# carrier_board_simplified.net
KiCad netlist of a schematic drawn in EAGLE
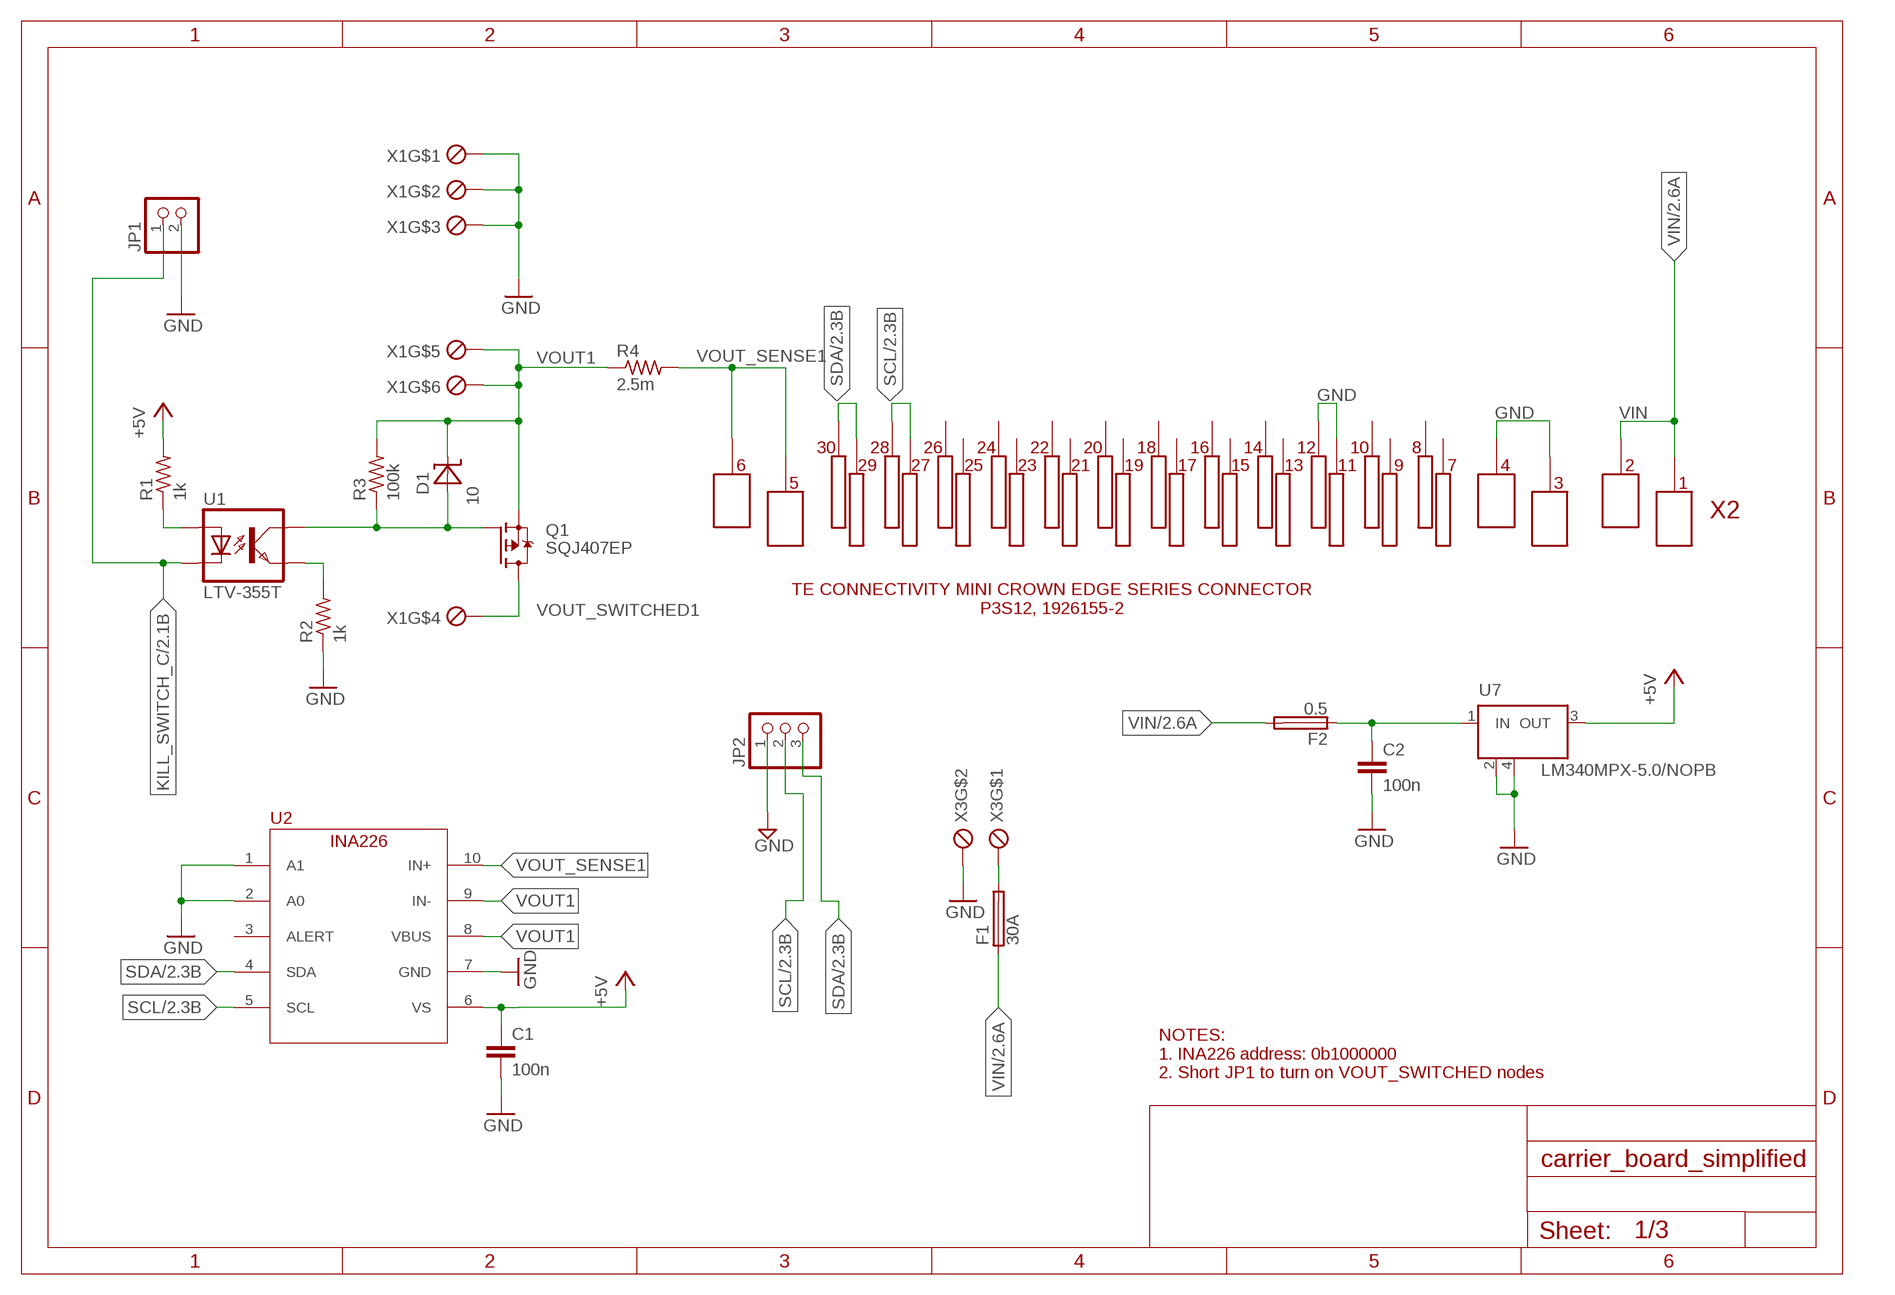
[diagram p0: schematic, sheet 1]
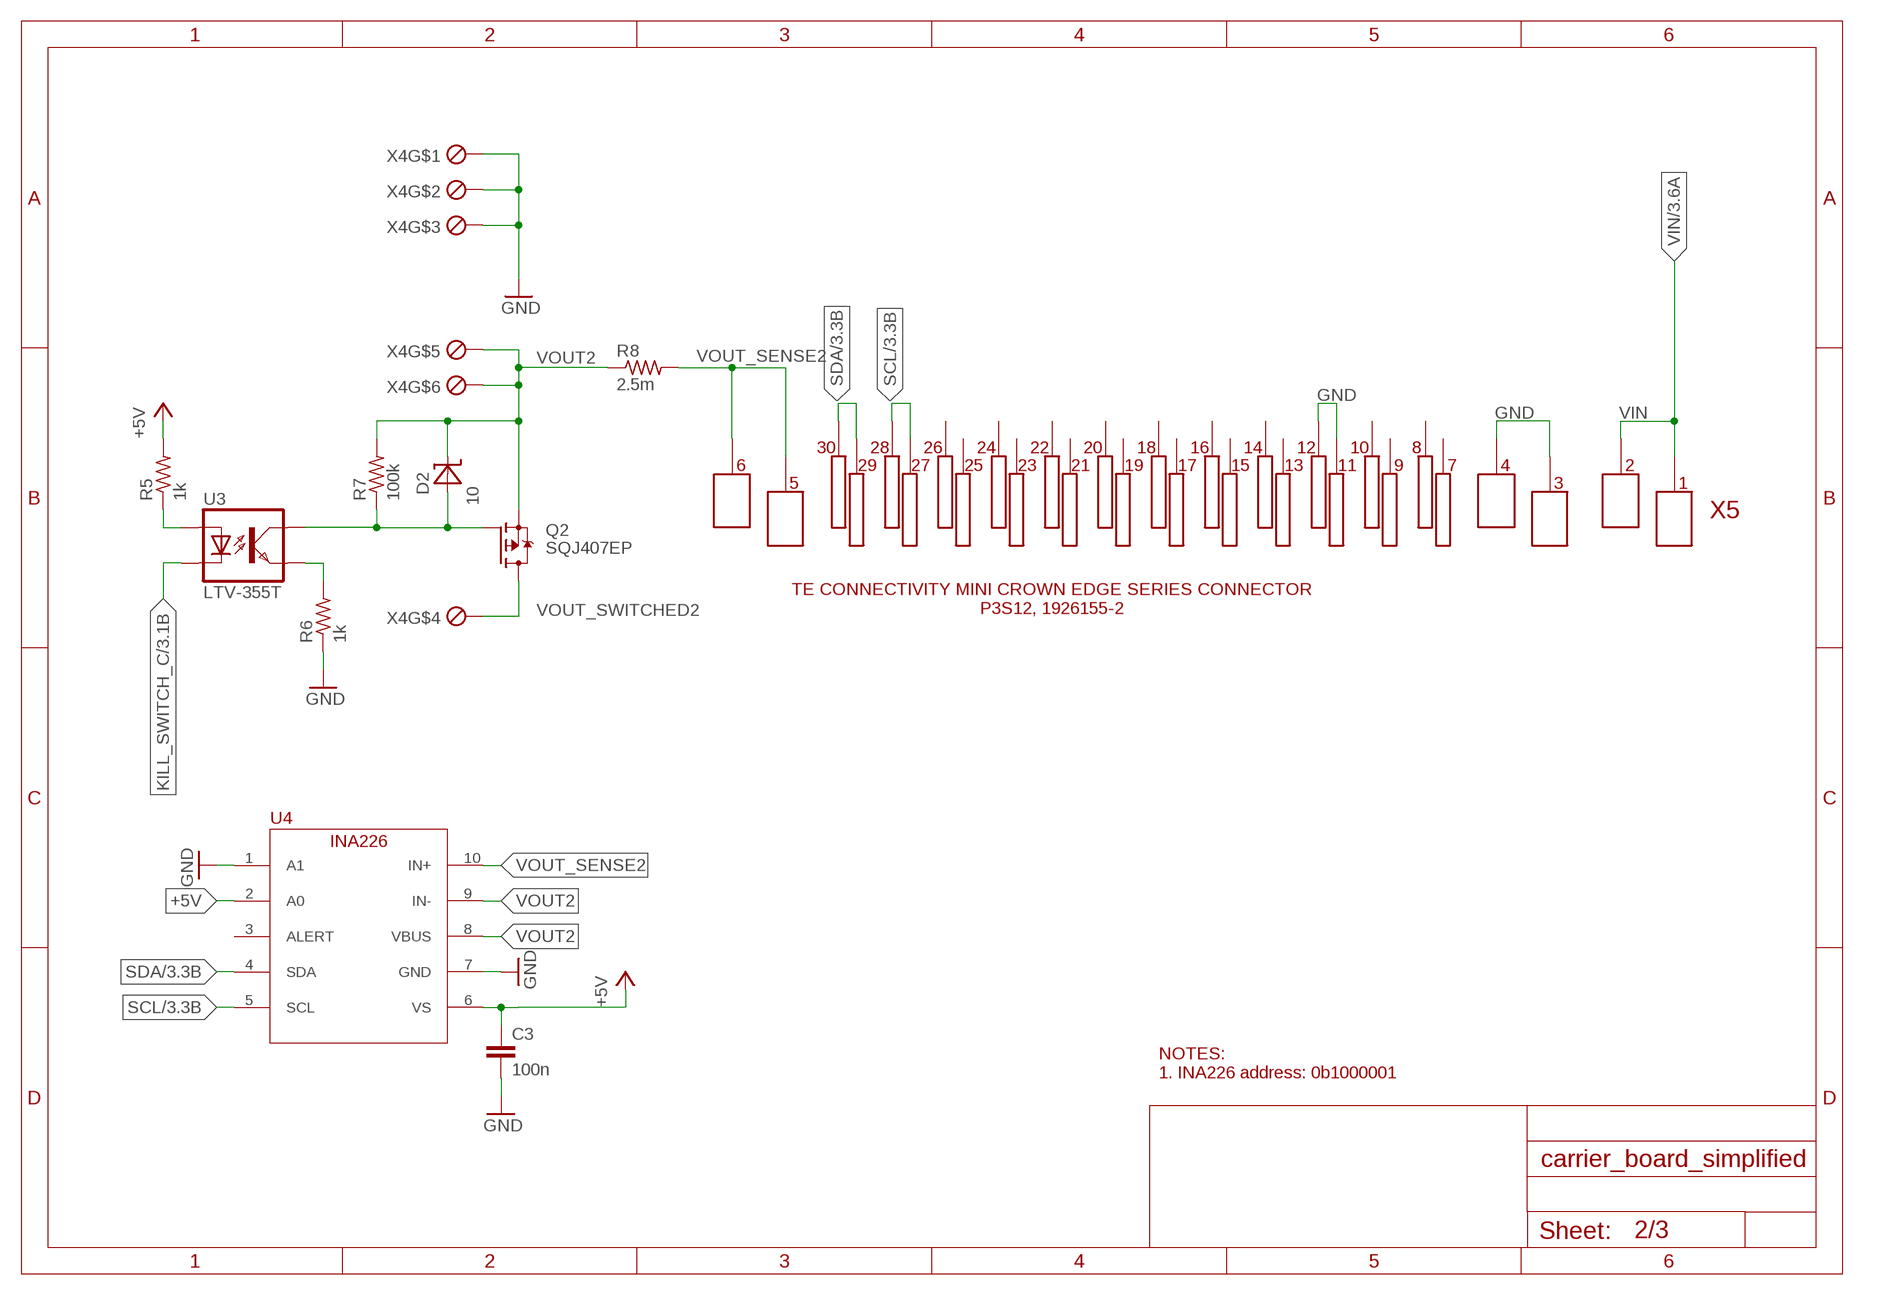
[diagram p1: schematic, sheet 2]
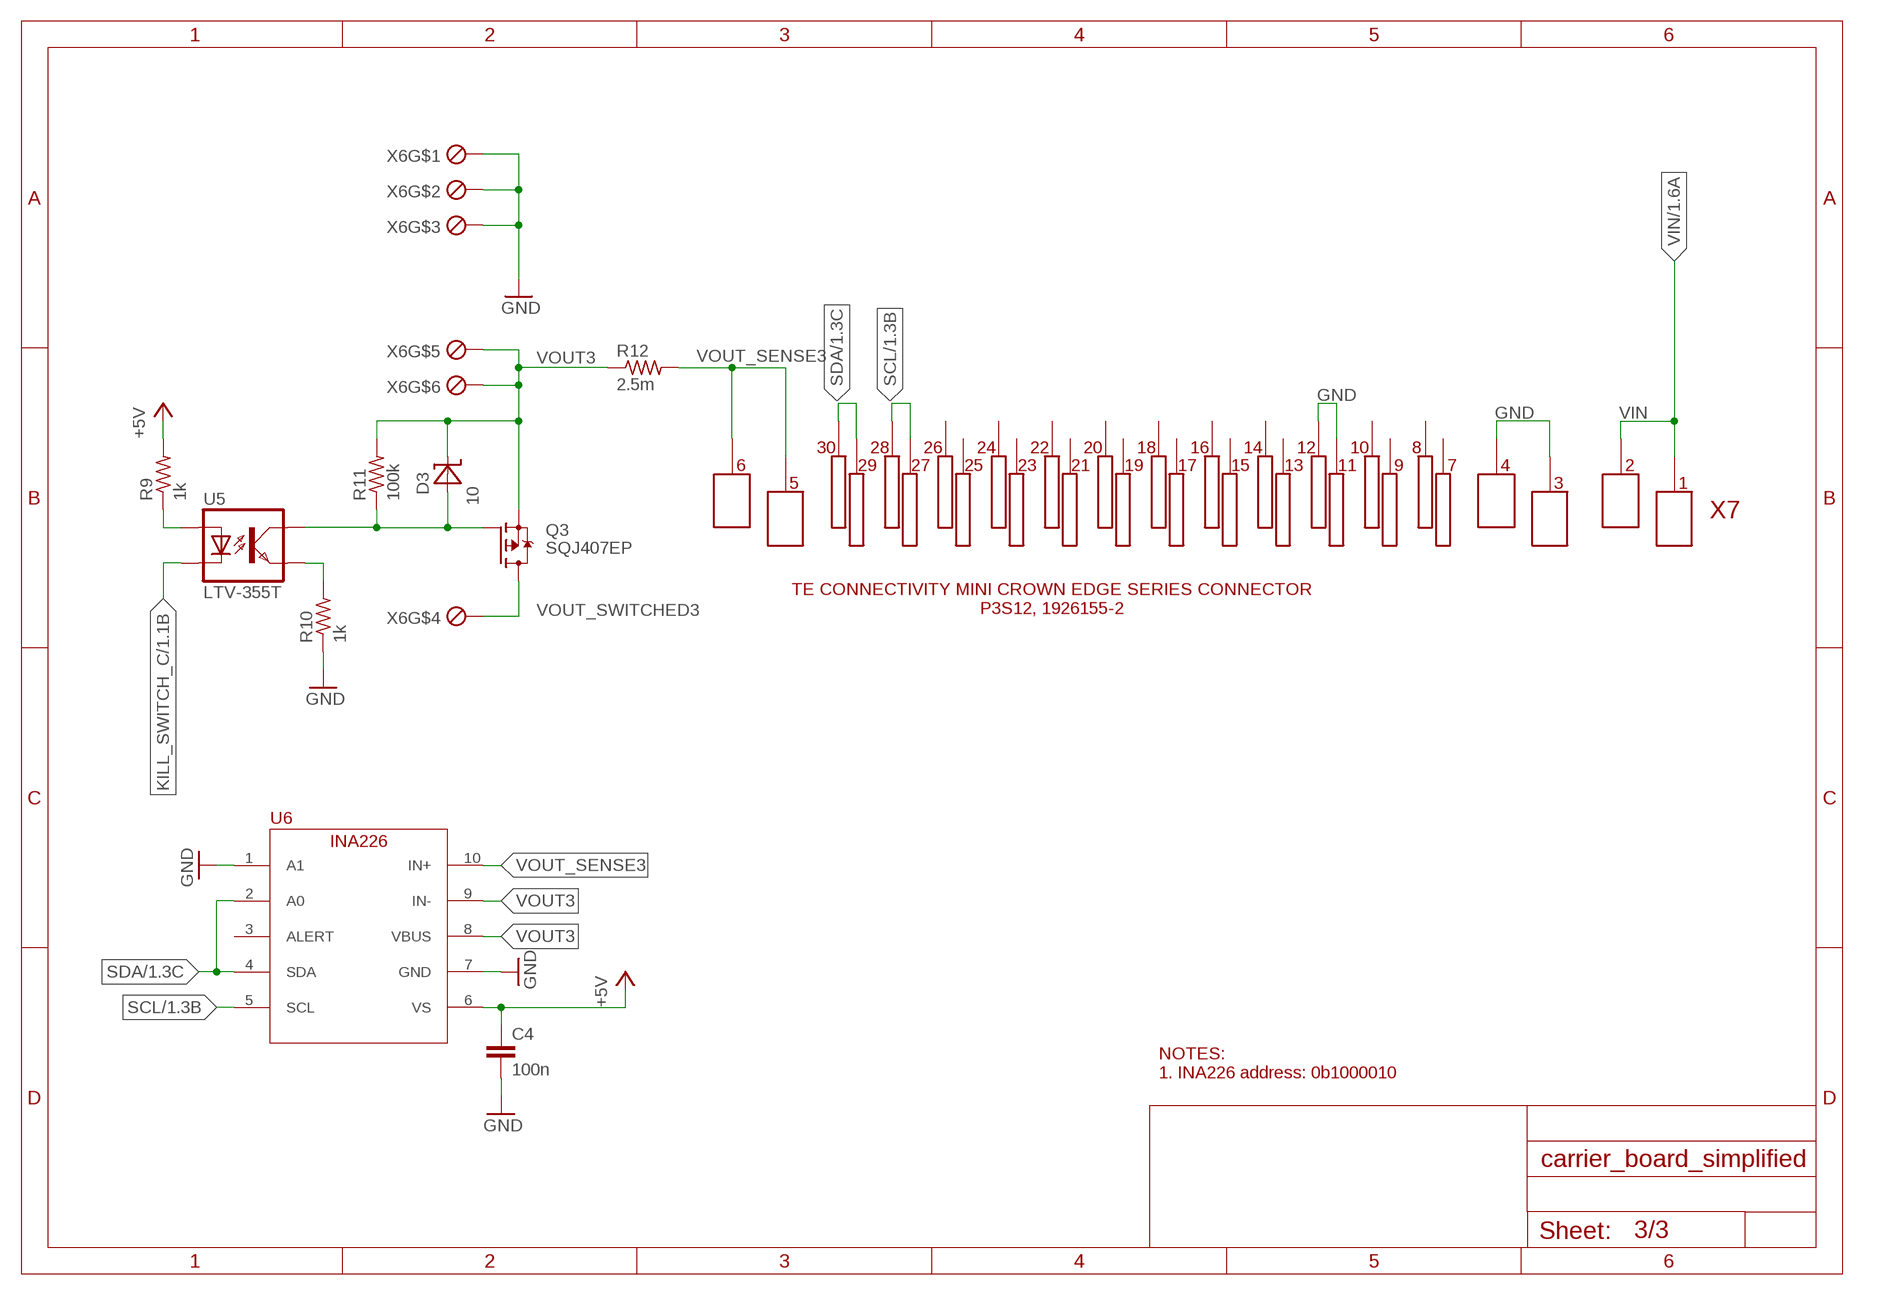
[diagram p2: schematic, sheet 3]

(export (version "E")
  (design (tool "Eeschema 10.0.6"))
  (components
    (comp (ref "C3")
      (value "100n")
      (footprint "eagle-import:C0603")
      (libsource (lib "eagle-import") (part "C-EUC0603"))
    )
    (comp (ref "D2")
      (value "10")
      (footprint "eagle-import:SOD123")
      (libsource (lib "eagle-import") (part "BZT52C10-TP"))
    )
    (comp (ref "Q2")
      (value "SQJ407EP")
      (footprint "eagle-import:POWERPAK_SO8L_SINGLE")
      (libsource (lib "eagle-import") (part "SQJ407EP"))
    )
    (comp (ref "R5")
      (value "1k")
      (footprint "eagle-import:R0603")
      (libsource (lib "eagle-import") (part "R-US_R0603"))
    )
    (comp (ref "R6")
      (value "1k")
      (footprint "eagle-import:R0603")
      (libsource (lib "eagle-import") (part "R-US_R0603"))
    )
    (comp (ref "R7")
      (value "100k")
      (footprint "eagle-import:R0603")
      (libsource (lib "eagle-import") (part "R-US_R0603"))
    )
    (comp (ref "R8")
      (value "2.5m")
      (footprint "eagle-import:R2512")
      (libsource (lib "eagle-import") (part "R-US_R2512"))
    )
    (comp (ref "U3")
      (value "LTV-355T")
      (footprint "eagle-import:SMD4")
      (libsource (lib "eagle-import") (part "LTV-355T"))
    )
    (comp (ref "U4")
      (value "INA226")
      (footprint "eagle-import:MSOP10")
      (libsource (lib "eagle-import") (part "INA226"))
    )
    (comp (ref "X4")
      (value "284391-6")
      (footprint "eagle-import:284391-6")
      (libsource (lib "eagle-import") (part "284391-6"))
    )
    (comp (ref "X5")
      (value "1926155-2_SOCK")
      (footprint "eagle-import:1926155-2_SOCK")
      (libsource (lib "eagle-import") (part "1926155-2_SOCK"))
    )
    (comp (ref "C1")
      (value "100n")
      (footprint "eagle-import:C0603")
      (libsource (lib "eagle-import") (part "C-EUC0603"))
    )
    (comp (ref "C2")
      (value "100n")
      (footprint "eagle-import:C0603")
      (libsource (lib "eagle-import") (part "C-EUC0603"))
    )
    (comp (ref "D1")
      (value "10")
      (footprint "eagle-import:SOD123")
      (libsource (lib "eagle-import") (part "BZT52C10-TP"))
    )
    (comp (ref "F1")
      (value "30A")
      (footprint "eagle-import:3557-10")
      (libsource (lib "eagle-import") (part "3557-10"))
    )
    (comp (ref "F2")
      (value "0.5")
      (footprint "eagle-import:R1206")
      (libsource (lib "eagle-import") (part "501_FUSE"))
    )
    (comp (ref "JP1")
      (value "PINHD-1X02_2.54-SMD-90°")
      (footprint "eagle-import:1X02SMD_90")
      (libsource (lib "eagle-import") (part "PINHD-1X02_2.54-SMD-90°"))
    )
    (comp (ref "JP2")
      (value "PINHD-1X03_2.54-SMD-90°")
      (footprint "eagle-import:1X03SMD_90")
      (libsource (lib "eagle-import") (part "PINHD-1X03_2.54-SMD-90°"))
    )
    (comp (ref "Q1")
      (value "SQJ407EP")
      (footprint "eagle-import:POWERPAK_SO8L_SINGLE")
      (libsource (lib "eagle-import") (part "SQJ407EP"))
    )
    (comp (ref "R1")
      (value "1k")
      (footprint "eagle-import:R0603")
      (libsource (lib "eagle-import") (part "R-US_R0603"))
    )
    (comp (ref "R2")
      (value "1k")
      (footprint "eagle-import:R0603")
      (libsource (lib "eagle-import") (part "R-US_R0603"))
    )
    (comp (ref "R3")
      (value "100k")
      (footprint "eagle-import:R0603")
      (libsource (lib "eagle-import") (part "R-US_R0603"))
    )
    (comp (ref "R4")
      (value "2.5m")
      (footprint "eagle-import:R2512")
      (libsource (lib "eagle-import") (part "R-US_R2512"))
    )
    (comp (ref "U1")
      (value "LTV-355T")
      (footprint "eagle-import:SMD4")
      (libsource (lib "eagle-import") (part "LTV-355T"))
    )
    (comp (ref "U2")
      (value "INA226")
      (footprint "eagle-import:MSOP10")
      (libsource (lib "eagle-import") (part "INA226"))
    )
    (comp (ref "U7")
      (value "LM340MPX-5.0/NOPB")
      (footprint "eagle-import:SOT223")
      (libsource (lib "eagle-import") (part "LM340S"))
    )
    (comp (ref "X1")
      (value "284391-6")
      (footprint "eagle-import:284391-6")
      (libsource (lib "eagle-import") (part "284391-6"))
    )
    (comp (ref "X2")
      (value "1926155-2_SOCK")
      (footprint "eagle-import:1926155-2_SOCK")
      (libsource (lib "eagle-import") (part "1926155-2_SOCK"))
    )
    (comp (ref "X3")
      (value "OSTT7020150")
      (footprint "eagle-import:OSTT7020150")
      (libsource (lib "eagle-import") (part "OSTT7020150"))
    )
    (comp (ref "C4")
      (value "100n")
      (footprint "eagle-import:C0603")
      (libsource (lib "eagle-import") (part "C-EUC0603"))
    )
    (comp (ref "D3")
      (value "10")
      (footprint "eagle-import:SOD123")
      (libsource (lib "eagle-import") (part "BZT52C10-TP"))
    )
    (comp (ref "Q3")
      (value "SQJ407EP")
      (footprint "eagle-import:POWERPAK_SO8L_SINGLE")
      (libsource (lib "eagle-import") (part "SQJ407EP"))
    )
    (comp (ref "R9")
      (value "1k")
      (footprint "eagle-import:R0603")
      (libsource (lib "eagle-import") (part "R-US_R0603"))
    )
    (comp (ref "R10")
      (value "1k")
      (footprint "eagle-import:R0603")
      (libsource (lib "eagle-import") (part "R-US_R0603"))
    )
    (comp (ref "R11")
      (value "100k")
      (footprint "eagle-import:R0603")
      (libsource (lib "eagle-import") (part "R-US_R0603"))
    )
    (comp (ref "R12")
      (value "2.5m")
      (footprint "eagle-import:R2512")
      (libsource (lib "eagle-import") (part "R-US_R2512"))
    )
    (comp (ref "U5")
      (value "LTV-355T")
      (footprint "eagle-import:SMD4")
      (libsource (lib "eagle-import") (part "LTV-355T"))
    )
    (comp (ref "U6")
      (value "INA226")
      (footprint "eagle-import:MSOP10")
      (libsource (lib "eagle-import") (part "INA226"))
    )
    (comp (ref "X6")
      (value "284391-6")
      (footprint "eagle-import:284391-6")
      (libsource (lib "eagle-import") (part "284391-6"))
    )
    (comp (ref "X7")
      (value "1926155-2_SOCK")
      (footprint "eagle-import:1926155-2_SOCK")
      (libsource (lib "eagle-import") (part "1926155-2_SOCK"))
    )
  )
  (nets
    (net (code "1") (name "+5V") (class "Default")
      (node (ref "C1") (pin "1") (pinfunction "1_1") (pintype "passive"))
      (node (ref "C3") (pin "1") (pinfunction "1_1") (pintype "passive"))
      (node (ref "C4") (pin "1") (pinfunction "1_1") (pintype "passive"))
      (node (ref "R1") (pin "2") (pinfunction "2_2") (pintype "passive"))
      (node (ref "R5") (pin "2") (pinfunction "2_2") (pintype "passive"))
      (node (ref "R9") (pin "2") (pinfunction "2_2") (pintype "passive"))
      (node (ref "U2") (pin "6") (pinfunction "VS_6") (pintype "bidirectional"))
      (node (ref "U4") (pin "2") (pinfunction "A0_2") (pintype "bidirectional"))
      (node (ref "U4") (pin "6") (pinfunction "VS_6") (pintype "bidirectional"))
      (node (ref "U6") (pin "6") (pinfunction "VS_6") (pintype "bidirectional"))
      (node (ref "U7") (pin "3") (pinfunction "OUT_3") (pintype "passive"))
    )
    (net (code "2") (name "GND") (class "Default")
      (node (ref "C1") (pin "2") (pinfunction "2_2") (pintype "passive"))
      (node (ref "C2") (pin "2") (pinfunction "2_2") (pintype "passive"))
      (node (ref "C3") (pin "2") (pinfunction "2_2") (pintype "passive"))
      (node (ref "C4") (pin "2") (pinfunction "2_2") (pintype "passive"))
      (node (ref "JP1") (pin "2") (pinfunction "2_2") (pintype "passive"))
      (node (ref "JP2") (pin "1") (pinfunction "1_1") (pintype "passive"))
      (node (ref "R10") (pin "1") (pinfunction "1_1") (pintype "passive"))
      (node (ref "R2") (pin "1") (pinfunction "1_1") (pintype "passive"))
      (node (ref "R6") (pin "1") (pinfunction "1_1") (pintype "passive"))
      (node (ref "U2") (pin "1") (pinfunction "A1_1") (pintype "bidirectional"))
      (node (ref "U2") (pin "2") (pinfunction "A0_2") (pintype "bidirectional"))
      (node (ref "U2") (pin "7") (pinfunction "GND_7") (pintype "bidirectional"))
      (node (ref "U4") (pin "1") (pinfunction "A1_1") (pintype "bidirectional"))
      (node (ref "U4") (pin "7") (pinfunction "GND_7") (pintype "bidirectional"))
      (node (ref "U6") (pin "1") (pinfunction "A1_1") (pintype "bidirectional"))
      (node (ref "U6") (pin "7") (pinfunction "GND_7") (pintype "bidirectional"))
      (node (ref "U7") (pin "2") (pinfunction "GND_2") (pintype "power_in"))
      (node (ref "U7") (pin "4") (pinfunction "GND_4") (pintype "power_in"))
      (node (ref "X1") (pin "P$1") (pinfunction "1_P$1") (pintype "passive"))
      (node (ref "X1") (pin "P$2") (pinfunction "1_P$2") (pintype "passive"))
      (node (ref "X1") (pin "P$3") (pinfunction "1_P$3") (pintype "passive"))
      (node (ref "X2") (pin "P$11") (pinfunction "P$11_P$11") (pintype "bidirectional"))
      (node (ref "X2") (pin "P$12") (pinfunction "P$12_P$12") (pintype "bidirectional"))
      (node (ref "X2") (pin "P$3_1") (pinfunction "P$3_P$3_1") (pintype "bidirectional"))
      (node (ref "X2") (pin "P$3_2") (pinfunction "P$3_P$3_2") (pintype "bidirectional"))
      (node (ref "X2") (pin "P$3_3") (pinfunction "P$3_P$3_3") (pintype "bidirectional"))
      (node (ref "X2") (pin "P$4_1") (pinfunction "P$4_P$4_1") (pintype "bidirectional"))
      (node (ref "X2") (pin "P$4_2") (pinfunction "P$4_P$4_2") (pintype "bidirectional"))
      (node (ref "X2") (pin "P$4_3") (pinfunction "P$4_P$4_3") (pintype "bidirectional"))
      (node (ref "X3") (pin "2") (pinfunction "1_2") (pintype "passive"))
      (node (ref "X4") (pin "P$1") (pinfunction "1_P$1") (pintype "passive"))
      (node (ref "X4") (pin "P$2") (pinfunction "1_P$2") (pintype "passive"))
      (node (ref "X4") (pin "P$3") (pinfunction "1_P$3") (pintype "passive"))
      (node (ref "X5") (pin "P$11") (pinfunction "P$11_P$11") (pintype "bidirectional"))
      (node (ref "X5") (pin "P$12") (pinfunction "P$12_P$12") (pintype "bidirectional"))
      (node (ref "X5") (pin "P$3_1") (pinfunction "P$3_P$3_1") (pintype "bidirectional"))
      (node (ref "X5") (pin "P$3_2") (pinfunction "P$3_P$3_2") (pintype "bidirectional"))
      (node (ref "X5") (pin "P$3_3") (pinfunction "P$3_P$3_3") (pintype "bidirectional"))
      (node (ref "X5") (pin "P$4_1") (pinfunction "P$4_P$4_1") (pintype "bidirectional"))
      (node (ref "X5") (pin "P$4_2") (pinfunction "P$4_P$4_2") (pintype "bidirectional"))
      (node (ref "X5") (pin "P$4_3") (pinfunction "P$4_P$4_3") (pintype "bidirectional"))
      (node (ref "X6") (pin "P$1") (pinfunction "1_P$1") (pintype "passive"))
      (node (ref "X6") (pin "P$2") (pinfunction "1_P$2") (pintype "passive"))
      (node (ref "X6") (pin "P$3") (pinfunction "1_P$3") (pintype "passive"))
      (node (ref "X7") (pin "P$11") (pinfunction "P$11_P$11") (pintype "bidirectional"))
      (node (ref "X7") (pin "P$12") (pinfunction "P$12_P$12") (pintype "bidirectional"))
      (node (ref "X7") (pin "P$3_1") (pinfunction "P$3_P$3_1") (pintype "bidirectional"))
      (node (ref "X7") (pin "P$3_2") (pinfunction "P$3_P$3_2") (pintype "bidirectional"))
      (node (ref "X7") (pin "P$3_3") (pinfunction "P$3_P$3_3") (pintype "bidirectional"))
      (node (ref "X7") (pin "P$4_1") (pinfunction "P$4_P$4_1") (pintype "bidirectional"))
      (node (ref "X7") (pin "P$4_2") (pinfunction "P$4_P$4_2") (pintype "bidirectional"))
      (node (ref "X7") (pin "P$4_3") (pinfunction "P$4_P$4_3") (pintype "bidirectional"))
    )
    (net (code "3") (name "KILL_SWITCH_C") (class "Default")
      (node (ref "JP1") (pin "1") (pinfunction "1_1") (pintype "passive"))
      (node (ref "U1") (pin "CATHODE") (pinfunction "C_CATHODE") (pintype "passive"))
      (node (ref "U3") (pin "CATHODE") (pinfunction "C_CATHODE") (pintype "passive"))
      (node (ref "U5") (pin "CATHODE") (pinfunction "C_CATHODE") (pintype "passive"))
    )
    (net (code "4") (name "Net-(D1-A)") (class "Default")
      (node (ref "D1") (pin "2") (pinfunction "A_2") (pintype "passive"))
      (node (ref "Q1") (pin "P$4") (pinfunction "G_P$4") (pintype "passive"))
      (node (ref "R3") (pin "1") (pinfunction "1_1") (pintype "passive"))
      (node (ref "U1") (pin "COLLECTOR") (pinfunction "COL_COLLECTOR") (pintype "passive"))
    )
    (net (code "5") (name "Net-(D2-A)") (class "Default")
      (node (ref "D2") (pin "2") (pinfunction "A_2") (pintype "passive"))
      (node (ref "Q2") (pin "P$4") (pinfunction "G_P$4") (pintype "passive"))
      (node (ref "R7") (pin "1") (pinfunction "1_1") (pintype "passive"))
      (node (ref "U3") (pin "COLLECTOR") (pinfunction "COL_COLLECTOR") (pintype "passive"))
    )
    (net (code "6") (name "Net-(D3-A)") (class "Default")
      (node (ref "D3") (pin "2") (pinfunction "A_2") (pintype "passive"))
      (node (ref "Q3") (pin "P$4") (pinfunction "G_P$4") (pintype "passive"))
      (node (ref "R11") (pin "1") (pinfunction "1_1") (pintype "passive"))
      (node (ref "U5") (pin "COLLECTOR") (pinfunction "COL_COLLECTOR") (pintype "passive"))
    )
    (net (code "7") (name "Net-(F1-2-PadP$3)") (class "Default")
      (node (ref "F1") (pin "P$3") (pinfunction "2_P$3") (pintype "passive"))
      (node (ref "F1") (pin "P$4") (pinfunction "2_P$4") (pintype "passive"))
      (node (ref "X3") (pin "1") (pinfunction "1_1") (pintype "passive"))
    )
    (net (code "8") (name "Net-(U1-A)") (class "Default")
      (node (ref "R1") (pin "1") (pinfunction "1_1") (pintype "passive"))
      (node (ref "U1") (pin "ANODE") (pinfunction "A_ANODE") (pintype "passive"))
    )
    (net (code "9") (name "Net-(U1-EMIT)") (class "Default")
      (node (ref "R2") (pin "2") (pinfunction "2_2") (pintype "passive"))
      (node (ref "U1") (pin "EMITTER") (pinfunction "EMIT_EMITTER") (pintype "passive"))
    )
    (net (code "10") (name "Net-(U3-A)") (class "Default")
      (node (ref "R5") (pin "1") (pinfunction "1_1") (pintype "passive"))
      (node (ref "U3") (pin "ANODE") (pinfunction "A_ANODE") (pintype "passive"))
    )
    (net (code "11") (name "Net-(U3-EMIT)") (class "Default")
      (node (ref "R6") (pin "2") (pinfunction "2_2") (pintype "passive"))
      (node (ref "U3") (pin "EMITTER") (pinfunction "EMIT_EMITTER") (pintype "passive"))
    )
    (net (code "12") (name "Net-(U5-A)") (class "Default")
      (node (ref "R9") (pin "1") (pinfunction "1_1") (pintype "passive"))
      (node (ref "U5") (pin "ANODE") (pinfunction "A_ANODE") (pintype "passive"))
    )
    (net (code "13") (name "Net-(U5-EMIT)") (class "Default")
      (node (ref "R10") (pin "2") (pinfunction "2_2") (pintype "passive"))
      (node (ref "U5") (pin "EMITTER") (pinfunction "EMIT_EMITTER") (pintype "passive"))
    )
    (net (code "14") (name "Net-(U7-IN)") (class "Default")
      (node (ref "C2") (pin "1") (pinfunction "1_1") (pintype "passive"))
      (node (ref "F2") (pin "1") (pinfunction "1_1") (pintype "passive"))
      (node (ref "U7") (pin "1") (pinfunction "IN_1") (pintype "input"))
    )
    (net (code "15") (name "SCL") (class "Default")
      (node (ref "JP2") (pin "2") (pinfunction "2_2") (pintype "passive"))
      (node (ref "U2") (pin "5") (pinfunction "SCL_5") (pintype "bidirectional"))
      (node (ref "U4") (pin "5") (pinfunction "SCL_5") (pintype "bidirectional"))
      (node (ref "U6") (pin "5") (pinfunction "SCL_5") (pintype "bidirectional"))
      (node (ref "X2") (pin "P$27") (pinfunction "P$27_P$27") (pintype "bidirectional"))
      (node (ref "X2") (pin "P$28") (pinfunction "P$28_P$28") (pintype "bidirectional"))
      (node (ref "X5") (pin "P$27") (pinfunction "P$27_P$27") (pintype "bidirectional"))
      (node (ref "X5") (pin "P$28") (pinfunction "P$28_P$28") (pintype "bidirectional"))
      (node (ref "X7") (pin "P$27") (pinfunction "P$27_P$27") (pintype "bidirectional"))
      (node (ref "X7") (pin "P$28") (pinfunction "P$28_P$28") (pintype "bidirectional"))
    )
    (net (code "16") (name "SDA") (class "Default")
      (node (ref "JP2") (pin "3") (pinfunction "3_3") (pintype "passive"))
      (node (ref "U2") (pin "4") (pinfunction "SDA_4") (pintype "bidirectional"))
      (node (ref "U4") (pin "4") (pinfunction "SDA_4") (pintype "bidirectional"))
      (node (ref "U6") (pin "2") (pinfunction "A0_2") (pintype "bidirectional"))
      (node (ref "U6") (pin "4") (pinfunction "SDA_4") (pintype "bidirectional"))
      (node (ref "X2") (pin "P$29") (pinfunction "P$29_P$29") (pintype "bidirectional"))
      (node (ref "X2") (pin "P$30") (pinfunction "P$30_P$30") (pintype "bidirectional"))
      (node (ref "X5") (pin "P$29") (pinfunction "P$29_P$29") (pintype "bidirectional"))
      (node (ref "X5") (pin "P$30") (pinfunction "P$30_P$30") (pintype "bidirectional"))
      (node (ref "X7") (pin "P$29") (pinfunction "P$29_P$29") (pintype "bidirectional"))
      (node (ref "X7") (pin "P$30") (pinfunction "P$30_P$30") (pintype "bidirectional"))
    )
    (net (code "17") (name "VIN") (class "Default")
      (node (ref "F1") (pin "P$1") (pinfunction "1_P$1") (pintype "passive"))
      (node (ref "F1") (pin "P$2") (pinfunction "1_P$2") (pintype "passive"))
      (node (ref "F2") (pin "2") (pinfunction "2_2") (pintype "passive"))
      (node (ref "X2") (pin "P$1_1") (pinfunction "P$1_P$1_1") (pintype "bidirectional"))
      (node (ref "X2") (pin "P$1_2") (pinfunction "P$1_P$1_2") (pintype "bidirectional"))
      (node (ref "X2") (pin "P$1_3") (pinfunction "P$1_P$1_3") (pintype "bidirectional"))
      (node (ref "X2") (pin "P$2_1") (pinfunction "P$2_P$2_1") (pintype "bidirectional"))
      (node (ref "X2") (pin "P$2_2") (pinfunction "P$2_P$2_2") (pintype "bidirectional"))
      (node (ref "X2") (pin "P$2_3") (pinfunction "P$2_P$2_3") (pintype "bidirectional"))
      (node (ref "X5") (pin "P$1_1") (pinfunction "P$1_P$1_1") (pintype "bidirectional"))
      (node (ref "X5") (pin "P$1_2") (pinfunction "P$1_P$1_2") (pintype "bidirectional"))
      (node (ref "X5") (pin "P$1_3") (pinfunction "P$1_P$1_3") (pintype "bidirectional"))
      (node (ref "X5") (pin "P$2_1") (pinfunction "P$2_P$2_1") (pintype "bidirectional"))
      (node (ref "X5") (pin "P$2_2") (pinfunction "P$2_P$2_2") (pintype "bidirectional"))
      (node (ref "X5") (pin "P$2_3") (pinfunction "P$2_P$2_3") (pintype "bidirectional"))
      (node (ref "X7") (pin "P$1_1") (pinfunction "P$1_P$1_1") (pintype "bidirectional"))
      (node (ref "X7") (pin "P$1_2") (pinfunction "P$1_P$1_2") (pintype "bidirectional"))
      (node (ref "X7") (pin "P$1_3") (pinfunction "P$1_P$1_3") (pintype "bidirectional"))
      (node (ref "X7") (pin "P$2_1") (pinfunction "P$2_P$2_1") (pintype "bidirectional"))
      (node (ref "X7") (pin "P$2_2") (pinfunction "P$2_P$2_2") (pintype "bidirectional"))
      (node (ref "X7") (pin "P$2_3") (pinfunction "P$2_P$2_3") (pintype "bidirectional"))
    )
    (net (code "18") (name "VOUT1") (class "Default")
      (node (ref "D1") (pin "1") (pinfunction "C_1") (pintype "passive"))
      (node (ref "Q1") (pin "P$1") (pinfunction "S_P$1") (pintype "passive"))
      (node (ref "Q1") (pin "P$2") (pinfunction "S_P$2") (pintype "passive"))
      (node (ref "Q1") (pin "P$3") (pinfunction "S_P$3") (pintype "passive"))
      (node (ref "R3") (pin "2") (pinfunction "2_2") (pintype "passive"))
      (node (ref "R4") (pin "1") (pinfunction "1_1") (pintype "passive"))
      (node (ref "U2") (pin "8") (pinfunction "VBUS_8") (pintype "bidirectional"))
      (node (ref "U2") (pin "9") (pinfunction "IN-_9") (pintype "bidirectional"))
      (node (ref "X1") (pin "P$5") (pinfunction "1_P$5") (pintype "passive"))
      (node (ref "X1") (pin "P$6") (pinfunction "1_P$6") (pintype "passive"))
    )
    (net (code "19") (name "VOUT2") (class "Default")
      (node (ref "D2") (pin "1") (pinfunction "C_1") (pintype "passive"))
      (node (ref "Q2") (pin "P$1") (pinfunction "S_P$1") (pintype "passive"))
      (node (ref "Q2") (pin "P$2") (pinfunction "S_P$2") (pintype "passive"))
      (node (ref "Q2") (pin "P$3") (pinfunction "S_P$3") (pintype "passive"))
      (node (ref "R7") (pin "2") (pinfunction "2_2") (pintype "passive"))
      (node (ref "R8") (pin "1") (pinfunction "1_1") (pintype "passive"))
      (node (ref "U4") (pin "8") (pinfunction "VBUS_8") (pintype "bidirectional"))
      (node (ref "U4") (pin "9") (pinfunction "IN-_9") (pintype "bidirectional"))
      (node (ref "X4") (pin "P$5") (pinfunction "1_P$5") (pintype "passive"))
      (node (ref "X4") (pin "P$6") (pinfunction "1_P$6") (pintype "passive"))
    )
    (net (code "20") (name "VOUT3") (class "Default")
      (node (ref "D3") (pin "1") (pinfunction "C_1") (pintype "passive"))
      (node (ref "Q3") (pin "P$1") (pinfunction "S_P$1") (pintype "passive"))
      (node (ref "Q3") (pin "P$2") (pinfunction "S_P$2") (pintype "passive"))
      (node (ref "Q3") (pin "P$3") (pinfunction "S_P$3") (pintype "passive"))
      (node (ref "R11") (pin "2") (pinfunction "2_2") (pintype "passive"))
      (node (ref "R12") (pin "1") (pinfunction "1_1") (pintype "passive"))
      (node (ref "U6") (pin "8") (pinfunction "VBUS_8") (pintype "bidirectional"))
      (node (ref "U6") (pin "9") (pinfunction "IN-_9") (pintype "bidirectional"))
      (node (ref "X6") (pin "P$5") (pinfunction "1_P$5") (pintype "passive"))
      (node (ref "X6") (pin "P$6") (pinfunction "1_P$6") (pintype "passive"))
    )
    (net (code "21") (name "VOUT_SENSE1") (class "Default")
      (node (ref "R4") (pin "2") (pinfunction "2_2") (pintype "passive"))
      (node (ref "U2") (pin "10") (pinfunction "IN+_10") (pintype "bidirectional"))
      (node (ref "X2") (pin "P$5_1") (pinfunction "P$5_P$5_1") (pintype "bidirectional"))
      (node (ref "X2") (pin "P$5_2") (pinfunction "P$5_P$5_2") (pintype "bidirectional"))
      (node (ref "X2") (pin "P$5_3") (pinfunction "P$5_P$5_3") (pintype "bidirectional"))
      (node (ref "X2") (pin "P$6_1") (pinfunction "P$6_P$6_1") (pintype "bidirectional"))
      (node (ref "X2") (pin "P$6_2") (pinfunction "P$6_P$6_2") (pintype "bidirectional"))
      (node (ref "X2") (pin "P$6_3") (pinfunction "P$6_P$6_3") (pintype "bidirectional"))
    )
    (net (code "22") (name "VOUT_SENSE2") (class "Default")
      (node (ref "R8") (pin "2") (pinfunction "2_2") (pintype "passive"))
      (node (ref "U4") (pin "10") (pinfunction "IN+_10") (pintype "bidirectional"))
      (node (ref "X5") (pin "P$5_1") (pinfunction "P$5_P$5_1") (pintype "bidirectional"))
      (node (ref "X5") (pin "P$5_2") (pinfunction "P$5_P$5_2") (pintype "bidirectional"))
      (node (ref "X5") (pin "P$5_3") (pinfunction "P$5_P$5_3") (pintype "bidirectional"))
      (node (ref "X5") (pin "P$6_1") (pinfunction "P$6_P$6_1") (pintype "bidirectional"))
      (node (ref "X5") (pin "P$6_2") (pinfunction "P$6_P$6_2") (pintype "bidirectional"))
      (node (ref "X5") (pin "P$6_3") (pinfunction "P$6_P$6_3") (pintype "bidirectional"))
    )
    (net (code "23") (name "VOUT_SENSE3") (class "Default")
      (node (ref "R12") (pin "2") (pinfunction "2_2") (pintype "passive"))
      (node (ref "U6") (pin "10") (pinfunction "IN+_10") (pintype "bidirectional"))
      (node (ref "X7") (pin "P$5_1") (pinfunction "P$5_P$5_1") (pintype "bidirectional"))
      (node (ref "X7") (pin "P$5_2") (pinfunction "P$5_P$5_2") (pintype "bidirectional"))
      (node (ref "X7") (pin "P$5_3") (pinfunction "P$5_P$5_3") (pintype "bidirectional"))
      (node (ref "X7") (pin "P$6_1") (pinfunction "P$6_P$6_1") (pintype "bidirectional"))
      (node (ref "X7") (pin "P$6_2") (pinfunction "P$6_P$6_2") (pintype "bidirectional"))
      (node (ref "X7") (pin "P$6_3") (pinfunction "P$6_P$6_3") (pintype "bidirectional"))
    )
    (net (code "24") (name "VOUT_SWITCHED1") (class "Default")
      (node (ref "Q1") (pin "P$5") (pinfunction "D_P$5") (pintype "passive"))
      (node (ref "Q1") (pin "P$6") (pinfunction "D_P$6") (pintype "passive"))
      (node (ref "Q1") (pin "P$7") (pinfunction "D_P$7") (pintype "passive"))
      (node (ref "Q1") (pin "P$8") (pinfunction "D_P$8") (pintype "passive"))
      (node (ref "X1") (pin "P$4") (pinfunction "1_P$4") (pintype "passive"))
    )
    (net (code "25") (name "VOUT_SWITCHED2") (class "Default")
      (node (ref "Q2") (pin "P$5") (pinfunction "D_P$5") (pintype "passive"))
      (node (ref "Q2") (pin "P$6") (pinfunction "D_P$6") (pintype "passive"))
      (node (ref "Q2") (pin "P$7") (pinfunction "D_P$7") (pintype "passive"))
      (node (ref "Q2") (pin "P$8") (pinfunction "D_P$8") (pintype "passive"))
      (node (ref "X4") (pin "P$4") (pinfunction "1_P$4") (pintype "passive"))
    )
    (net (code "26") (name "VOUT_SWITCHED3") (class "Default")
      (node (ref "Q3") (pin "P$5") (pinfunction "D_P$5") (pintype "passive"))
      (node (ref "Q3") (pin "P$6") (pinfunction "D_P$6") (pintype "passive"))
      (node (ref "Q3") (pin "P$7") (pinfunction "D_P$7") (pintype "passive"))
      (node (ref "Q3") (pin "P$8") (pinfunction "D_P$8") (pintype "passive"))
      (node (ref "X6") (pin "P$4") (pinfunction "1_P$4") (pintype "passive"))
    )
    (net (code "27") (name "unconnected-(U2-ALERT-Pad3)") (class "Default")
      (node (ref "U2") (pin "3") (pinfunction "ALERT_3") (pintype "bidirectional"))
    )
    (net (code "28") (name "unconnected-(U4-ALERT-Pad3)") (class "Default")
      (node (ref "U4") (pin "3") (pinfunction "ALERT_3") (pintype "bidirectional"))
    )
    (net (code "29") (name "unconnected-(U6-ALERT-Pad3)") (class "Default")
      (node (ref "U6") (pin "3") (pinfunction "ALERT_3") (pintype "bidirectional"))
    )
    (net (code "30") (name "unconnected-(X2-PadP$7)") (class "Default")
      (node (ref "X2") (pin "P$7") (pinfunction "P$7_P$7") (pintype "bidirectional"))
    )
    (net (code "31") (name "unconnected-(X2-PadP$8)") (class "Default")
      (node (ref "X2") (pin "P$8") (pinfunction "P$8_P$8") (pintype "bidirectional"))
    )
    (net (code "32") (name "unconnected-(X2-PadP$9)") (class "Default")
      (node (ref "X2") (pin "P$9") (pinfunction "P$9_P$9") (pintype "bidirectional"))
    )
    (net (code "33") (name "unconnected-(X2-PadP$10)") (class "Default")
      (node (ref "X2") (pin "P$10") (pinfunction "P$10_P$10") (pintype "bidirectional"))
    )
    (net (code "34") (name "unconnected-(X2-PadP$13)") (class "Default")
      (node (ref "X2") (pin "P$13") (pinfunction "P$13_P$13") (pintype "bidirectional"))
    )
    (net (code "35") (name "unconnected-(X2-PadP$14)") (class "Default")
      (node (ref "X2") (pin "P$14") (pinfunction "P$14_P$14") (pintype "bidirectional"))
    )
    (net (code "36") (name "unconnected-(X2-PadP$15)") (class "Default")
      (node (ref "X2") (pin "P$15") (pinfunction "P$15_P$15") (pintype "bidirectional"))
    )
    (net (code "37") (name "unconnected-(X2-PadP$16)") (class "Default")
      (node (ref "X2") (pin "P$16") (pinfunction "P$16_P$16") (pintype "bidirectional"))
    )
    (net (code "38") (name "unconnected-(X2-PadP$17)") (class "Default")
      (node (ref "X2") (pin "P$17") (pinfunction "P$17_P$17") (pintype "bidirectional"))
    )
    (net (code "39") (name "unconnected-(X2-PadP$18)") (class "Default")
      (node (ref "X2") (pin "P$18") (pinfunction "P$18_P$18") (pintype "bidirectional"))
    )
    (net (code "40") (name "unconnected-(X2-PadP$19)") (class "Default")
      (node (ref "X2") (pin "P$19") (pinfunction "P$19_P$19") (pintype "bidirectional"))
    )
    (net (code "41") (name "unconnected-(X2-PadP$20)") (class "Default")
      (node (ref "X2") (pin "P$20") (pinfunction "P$20_P$20") (pintype "bidirectional"))
    )
    (net (code "42") (name "unconnected-(X2-PadP$21)") (class "Default")
      (node (ref "X2") (pin "P$21") (pinfunction "P$21_P$21") (pintype "bidirectional"))
    )
    (net (code "43") (name "unconnected-(X2-PadP$22)") (class "Default")
      (node (ref "X2") (pin "P$22") (pinfunction "P$22_P$22") (pintype "bidirectional"))
    )
    (net (code "44") (name "unconnected-(X2-PadP$23)") (class "Default")
      (node (ref "X2") (pin "P$23") (pinfunction "P$23_P$23") (pintype "bidirectional"))
    )
    (net (code "45") (name "unconnected-(X2-PadP$24)") (class "Default")
      (node (ref "X2") (pin "P$24") (pinfunction "P$24_P$24") (pintype "bidirectional"))
    )
    (net (code "46") (name "unconnected-(X2-PadP$25)") (class "Default")
      (node (ref "X2") (pin "P$25") (pinfunction "P$25_P$25") (pintype "bidirectional"))
    )
    (net (code "47") (name "unconnected-(X2-PadP$26)") (class "Default")
      (node (ref "X2") (pin "P$26") (pinfunction "P$26_P$26") (pintype "bidirectional"))
    )
    (net (code "48") (name "unconnected-(X5-PadP$7)") (class "Default")
      (node (ref "X5") (pin "P$7") (pinfunction "P$7_P$7") (pintype "bidirectional"))
    )
    (net (code "49") (name "unconnected-(X5-PadP$8)") (class "Default")
      (node (ref "X5") (pin "P$8") (pinfunction "P$8_P$8") (pintype "bidirectional"))
    )
    (net (code "50") (name "unconnected-(X5-PadP$9)") (class "Default")
      (node (ref "X5") (pin "P$9") (pinfunction "P$9_P$9") (pintype "bidirectional"))
    )
    (net (code "51") (name "unconnected-(X5-PadP$10)") (class "Default")
      (node (ref "X5") (pin "P$10") (pinfunction "P$10_P$10") (pintype "bidirectional"))
    )
    (net (code "52") (name "unconnected-(X5-PadP$13)") (class "Default")
      (node (ref "X5") (pin "P$13") (pinfunction "P$13_P$13") (pintype "bidirectional"))
    )
    (net (code "53") (name "unconnected-(X5-PadP$14)") (class "Default")
      (node (ref "X5") (pin "P$14") (pinfunction "P$14_P$14") (pintype "bidirectional"))
    )
    (net (code "54") (name "unconnected-(X5-PadP$15)") (class "Default")
      (node (ref "X5") (pin "P$15") (pinfunction "P$15_P$15") (pintype "bidirectional"))
    )
    (net (code "55") (name "unconnected-(X5-PadP$16)") (class "Default")
      (node (ref "X5") (pin "P$16") (pinfunction "P$16_P$16") (pintype "bidirectional"))
    )
    (net (code "56") (name "unconnected-(X5-PadP$17)") (class "Default")
      (node (ref "X5") (pin "P$17") (pinfunction "P$17_P$17") (pintype "bidirectional"))
    )
    (net (code "57") (name "unconnected-(X5-PadP$18)") (class "Default")
      (node (ref "X5") (pin "P$18") (pinfunction "P$18_P$18") (pintype "bidirectional"))
    )
    (net (code "58") (name "unconnected-(X5-PadP$19)") (class "Default")
      (node (ref "X5") (pin "P$19") (pinfunction "P$19_P$19") (pintype "bidirectional"))
    )
    (net (code "59") (name "unconnected-(X5-PadP$20)") (class "Default")
      (node (ref "X5") (pin "P$20") (pinfunction "P$20_P$20") (pintype "bidirectional"))
    )
    (net (code "60") (name "unconnected-(X5-PadP$21)") (class "Default")
      (node (ref "X5") (pin "P$21") (pinfunction "P$21_P$21") (pintype "bidirectional"))
    )
    (net (code "61") (name "unconnected-(X5-PadP$22)") (class "Default")
      (node (ref "X5") (pin "P$22") (pinfunction "P$22_P$22") (pintype "bidirectional"))
    )
    (net (code "62") (name "unconnected-(X5-PadP$23)") (class "Default")
      (node (ref "X5") (pin "P$23") (pinfunction "P$23_P$23") (pintype "bidirectional"))
    )
    (net (code "63") (name "unconnected-(X5-PadP$24)") (class "Default")
      (node (ref "X5") (pin "P$24") (pinfunction "P$24_P$24") (pintype "bidirectional"))
    )
    (net (code "64") (name "unconnected-(X5-PadP$25)") (class "Default")
      (node (ref "X5") (pin "P$25") (pinfunction "P$25_P$25") (pintype "bidirectional"))
    )
    (net (code "65") (name "unconnected-(X5-PadP$26)") (class "Default")
      (node (ref "X5") (pin "P$26") (pinfunction "P$26_P$26") (pintype "bidirectional"))
    )
    (net (code "66") (name "unconnected-(X7-PadP$7)") (class "Default")
      (node (ref "X7") (pin "P$7") (pinfunction "P$7_P$7") (pintype "bidirectional"))
    )
    (net (code "67") (name "unconnected-(X7-PadP$8)") (class "Default")
      (node (ref "X7") (pin "P$8") (pinfunction "P$8_P$8") (pintype "bidirectional"))
    )
    (net (code "68") (name "unconnected-(X7-PadP$9)") (class "Default")
      (node (ref "X7") (pin "P$9") (pinfunction "P$9_P$9") (pintype "bidirectional"))
    )
    (net (code "69") (name "unconnected-(X7-PadP$10)") (class "Default")
      (node (ref "X7") (pin "P$10") (pinfunction "P$10_P$10") (pintype "bidirectional"))
    )
    (net (code "70") (name "unconnected-(X7-PadP$13)") (class "Default")
      (node (ref "X7") (pin "P$13") (pinfunction "P$13_P$13") (pintype "bidirectional"))
    )
    (net (code "71") (name "unconnected-(X7-PadP$14)") (class "Default")
      (node (ref "X7") (pin "P$14") (pinfunction "P$14_P$14") (pintype "bidirectional"))
    )
    (net (code "72") (name "unconnected-(X7-PadP$15)") (class "Default")
      (node (ref "X7") (pin "P$15") (pinfunction "P$15_P$15") (pintype "bidirectional"))
    )
    (net (code "73") (name "unconnected-(X7-PadP$16)") (class "Default")
      (node (ref "X7") (pin "P$16") (pinfunction "P$16_P$16") (pintype "bidirectional"))
    )
    (net (code "74") (name "unconnected-(X7-PadP$17)") (class "Default")
      (node (ref "X7") (pin "P$17") (pinfunction "P$17_P$17") (pintype "bidirectional"))
    )
    (net (code "75") (name "unconnected-(X7-PadP$18)") (class "Default")
      (node (ref "X7") (pin "P$18") (pinfunction "P$18_P$18") (pintype "bidirectional"))
    )
    (net (code "76") (name "unconnected-(X7-PadP$19)") (class "Default")
      (node (ref "X7") (pin "P$19") (pinfunction "P$19_P$19") (pintype "bidirectional"))
    )
    (net (code "77") (name "unconnected-(X7-PadP$20)") (class "Default")
      (node (ref "X7") (pin "P$20") (pinfunction "P$20_P$20") (pintype "bidirectional"))
    )
    (net (code "78") (name "unconnected-(X7-PadP$21)") (class "Default")
      (node (ref "X7") (pin "P$21") (pinfunction "P$21_P$21") (pintype "bidirectional"))
    )
    (net (code "79") (name "unconnected-(X7-PadP$22)") (class "Default")
      (node (ref "X7") (pin "P$22") (pinfunction "P$22_P$22") (pintype "bidirectional"))
    )
    (net (code "80") (name "unconnected-(X7-PadP$23)") (class "Default")
      (node (ref "X7") (pin "P$23") (pinfunction "P$23_P$23") (pintype "bidirectional"))
    )
    (net (code "81") (name "unconnected-(X7-PadP$24)") (class "Default")
      (node (ref "X7") (pin "P$24") (pinfunction "P$24_P$24") (pintype "bidirectional"))
    )
    (net (code "82") (name "unconnected-(X7-PadP$25)") (class "Default")
      (node (ref "X7") (pin "P$25") (pinfunction "P$25_P$25") (pintype "bidirectional"))
    )
    (net (code "83") (name "unconnected-(X7-PadP$26)") (class "Default")
      (node (ref "X7") (pin "P$26") (pinfunction "P$26_P$26") (pintype "bidirectional"))
    )
  )
)
